# FPGA_interface.net
KiCad netlist of a schematic drawn in Altium Designer
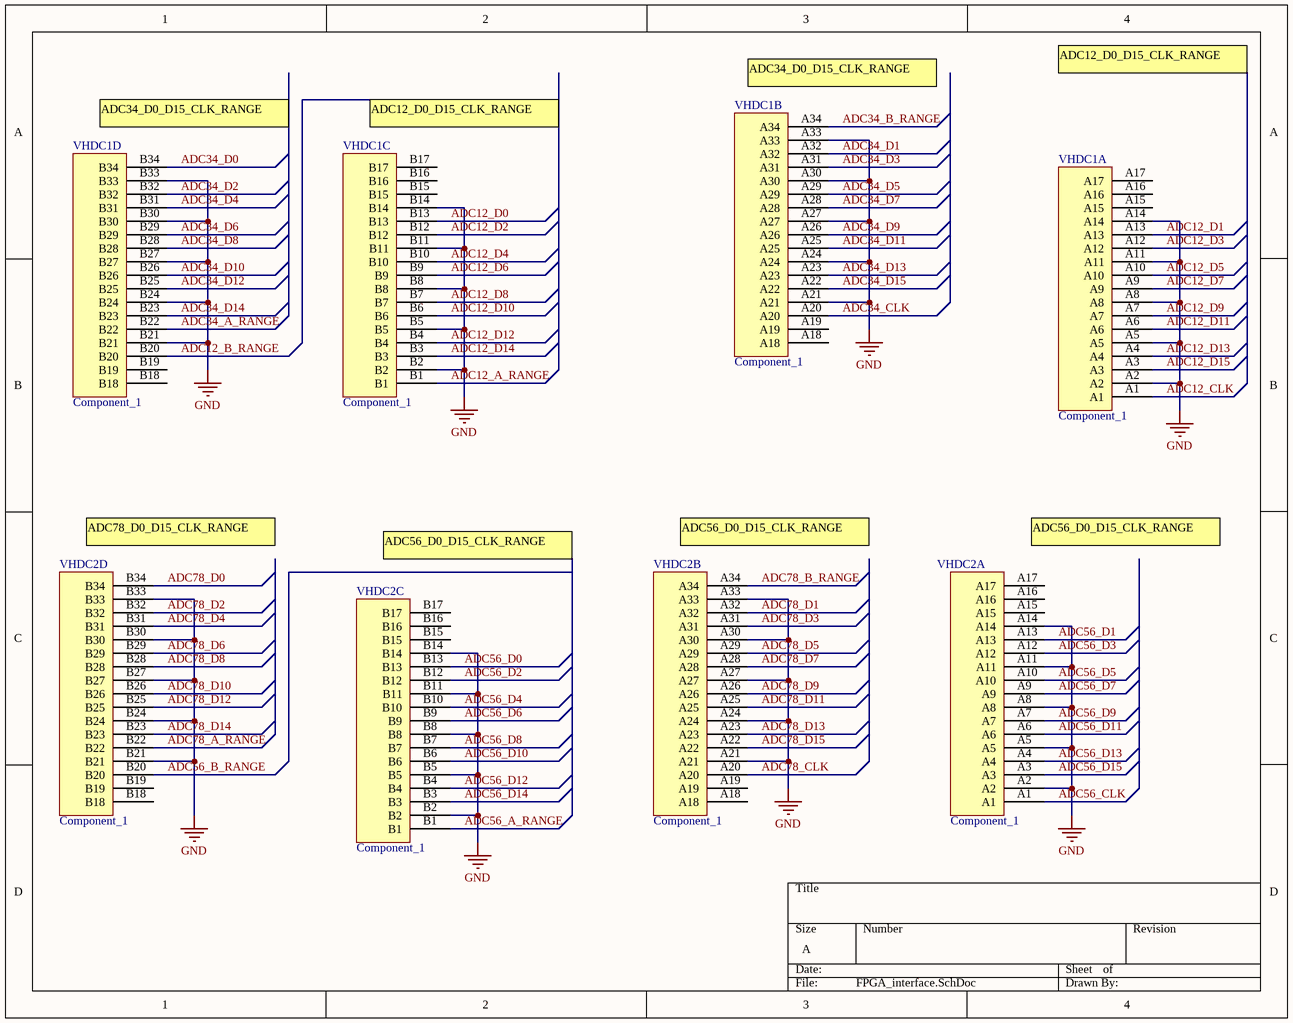
[diagram p0: FPGA_interface.SchDoc]

(export (version "E")
  (design (tool "Eeschema 10.0.6"))
  (components
    (comp (ref "VHDC1")
      (value "Component_1")
      (footprint "VHDCP-68-01-M-EM: PLUG")
      (description "VHDC_connector")
      (libsource (lib "MQP_lib") (part "Component_1"))
    )
    (comp (ref "VHDC2")
      (value "Component_1")
      (footprint "VHDCP-68-01-M-EM: PLUG")
      (description "VHDC_connector")
      (libsource (lib "MQP_lib") (part "Component_1"))
    )
  )
  (nets
    (net (code "1") (name "/ADC12_A_RANGE") (class "Default")
      (node (ref "VHDC1") (pin "B1") (pinfunction "B1_B1") (pintype "passive"))
    )
    (net (code "2") (name "/ADC12_B_RANGE") (class "Default")
      (node (ref "VHDC1") (pin "B20") (pinfunction "B20_B20") (pintype "passive"))
    )
    (net (code "3") (name "/ADC12_CLK") (class "Default")
      (node (ref "VHDC1") (pin "A1") (pinfunction "A1_A1") (pintype "passive"))
    )
    (net (code "4") (name "/ADC12_D0") (class "Default")
      (node (ref "VHDC1") (pin "B13") (pinfunction "B13_B13") (pintype "passive"))
    )
    (net (code "5") (name "/ADC12_D1") (class "Default")
      (node (ref "VHDC1") (pin "A13") (pinfunction "A13_A13") (pintype "passive"))
    )
    (net (code "6") (name "/ADC12_D2") (class "Default")
      (node (ref "VHDC1") (pin "B12") (pinfunction "B12_B12") (pintype "passive"))
    )
    (net (code "7") (name "/ADC12_D3") (class "Default")
      (node (ref "VHDC1") (pin "A12") (pinfunction "A12_A12") (pintype "passive"))
    )
    (net (code "8") (name "/ADC12_D4") (class "Default")
      (node (ref "VHDC1") (pin "B10") (pinfunction "B10_B10") (pintype "passive"))
    )
    (net (code "9") (name "/ADC12_D5") (class "Default")
      (node (ref "VHDC1") (pin "A10") (pinfunction "A10_A10") (pintype "passive"))
    )
    (net (code "10") (name "/ADC12_D6") (class "Default")
      (node (ref "VHDC1") (pin "B9") (pinfunction "B9_B9") (pintype "passive"))
    )
    (net (code "11") (name "/ADC12_D7") (class "Default")
      (node (ref "VHDC1") (pin "A9") (pinfunction "A9_A9") (pintype "passive"))
    )
    (net (code "12") (name "/ADC12_D8") (class "Default")
      (node (ref "VHDC1") (pin "B7") (pinfunction "B7_B7") (pintype "passive"))
    )
    (net (code "13") (name "/ADC12_D9") (class "Default")
      (node (ref "VHDC1") (pin "A7") (pinfunction "A7_A7") (pintype "passive"))
    )
    (net (code "14") (name "/ADC12_D10") (class "Default")
      (node (ref "VHDC1") (pin "B6") (pinfunction "B6_B6") (pintype "passive"))
    )
    (net (code "15") (name "/ADC12_D11") (class "Default")
      (node (ref "VHDC1") (pin "A6") (pinfunction "A6_A6") (pintype "passive"))
    )
    (net (code "16") (name "/ADC12_D12") (class "Default")
      (node (ref "VHDC1") (pin "B4") (pinfunction "B4_B4") (pintype "passive"))
    )
    (net (code "17") (name "/ADC12_D13") (class "Default")
      (node (ref "VHDC1") (pin "A4") (pinfunction "A4_A4") (pintype "passive"))
    )
    (net (code "18") (name "/ADC12_D14") (class "Default")
      (node (ref "VHDC1") (pin "B3") (pinfunction "B3_B3") (pintype "passive"))
    )
    (net (code "19") (name "/ADC12_D15") (class "Default")
      (node (ref "VHDC1") (pin "A3") (pinfunction "A3_A3") (pintype "passive"))
    )
    (net (code "20") (name "/ADC34_A_RANGE") (class "Default")
      (node (ref "VHDC1") (pin "B22") (pinfunction "B22_B22") (pintype "passive"))
    )
    (net (code "21") (name "/ADC34_B_RANGE") (class "Default")
      (node (ref "VHDC1") (pin "A34") (pinfunction "A34_A34") (pintype "passive"))
    )
    (net (code "22") (name "/ADC34_CLK") (class "Default")
      (node (ref "VHDC1") (pin "A20") (pinfunction "A20_A20") (pintype "passive"))
    )
    (net (code "23") (name "/ADC34_D0") (class "Default")
      (node (ref "VHDC1") (pin "B34") (pinfunction "B34_B34") (pintype "passive"))
    )
    (net (code "24") (name "/ADC34_D1") (class "Default")
      (node (ref "VHDC1") (pin "A32") (pinfunction "A32_A32") (pintype "passive"))
    )
    (net (code "25") (name "/ADC34_D2") (class "Default")
      (node (ref "VHDC1") (pin "B32") (pinfunction "B32_B32") (pintype "passive"))
    )
    (net (code "26") (name "/ADC34_D3") (class "Default")
      (node (ref "VHDC1") (pin "A31") (pinfunction "A31_A31") (pintype "passive"))
    )
    (net (code "27") (name "/ADC34_D4") (class "Default")
      (node (ref "VHDC1") (pin "B31") (pinfunction "B31_B31") (pintype "passive"))
    )
    (net (code "28") (name "/ADC34_D5") (class "Default")
      (node (ref "VHDC1") (pin "A29") (pinfunction "A29_A29") (pintype "passive"))
    )
    (net (code "29") (name "/ADC34_D6") (class "Default")
      (node (ref "VHDC1") (pin "B29") (pinfunction "B29_B29") (pintype "passive"))
    )
    (net (code "30") (name "/ADC34_D7") (class "Default")
      (node (ref "VHDC1") (pin "A28") (pinfunction "A28_A28") (pintype "passive"))
    )
    (net (code "31") (name "/ADC34_D8") (class "Default")
      (node (ref "VHDC1") (pin "B28") (pinfunction "B28_B28") (pintype "passive"))
    )
    (net (code "32") (name "/ADC34_D9") (class "Default")
      (node (ref "VHDC1") (pin "A26") (pinfunction "A26_A26") (pintype "passive"))
    )
    (net (code "33") (name "/ADC34_D10") (class "Default")
      (node (ref "VHDC1") (pin "B26") (pinfunction "B26_B26") (pintype "passive"))
    )
    (net (code "34") (name "/ADC34_D11") (class "Default")
      (node (ref "VHDC1") (pin "A25") (pinfunction "A25_A25") (pintype "passive"))
    )
    (net (code "35") (name "/ADC34_D12") (class "Default")
      (node (ref "VHDC1") (pin "B25") (pinfunction "B25_B25") (pintype "passive"))
    )
    (net (code "36") (name "/ADC34_D13") (class "Default")
      (node (ref "VHDC1") (pin "A23") (pinfunction "A23_A23") (pintype "passive"))
    )
    (net (code "37") (name "/ADC34_D14") (class "Default")
      (node (ref "VHDC1") (pin "B23") (pinfunction "B23_B23") (pintype "passive"))
    )
    (net (code "38") (name "/ADC34_D15") (class "Default")
      (node (ref "VHDC1") (pin "A22") (pinfunction "A22_A22") (pintype "passive"))
    )
    (net (code "39") (name "/ADC56_A_RANGE") (class "Default")
      (node (ref "VHDC2") (pin "B1") (pinfunction "B1_B1") (pintype "passive"))
    )
    (net (code "40") (name "/ADC56_B_RANGE") (class "Default")
      (node (ref "VHDC2") (pin "B20") (pinfunction "B20_B20") (pintype "passive"))
    )
    (net (code "41") (name "/ADC56_CLK") (class "Default")
      (node (ref "VHDC2") (pin "A1") (pinfunction "A1_A1") (pintype "passive"))
    )
    (net (code "42") (name "/ADC56_D0") (class "Default")
      (node (ref "VHDC2") (pin "B13") (pinfunction "B13_B13") (pintype "passive"))
    )
    (net (code "43") (name "/ADC56_D1") (class "Default")
      (node (ref "VHDC2") (pin "A13") (pinfunction "A13_A13") (pintype "passive"))
    )
    (net (code "44") (name "/ADC56_D2") (class "Default")
      (node (ref "VHDC2") (pin "B12") (pinfunction "B12_B12") (pintype "passive"))
    )
    (net (code "45") (name "/ADC56_D3") (class "Default")
      (node (ref "VHDC2") (pin "A12") (pinfunction "A12_A12") (pintype "passive"))
    )
    (net (code "46") (name "/ADC56_D4") (class "Default")
      (node (ref "VHDC2") (pin "B10") (pinfunction "B10_B10") (pintype "passive"))
    )
    (net (code "47") (name "/ADC56_D5") (class "Default")
      (node (ref "VHDC2") (pin "A10") (pinfunction "A10_A10") (pintype "passive"))
    )
    (net (code "48") (name "/ADC56_D6") (class "Default")
      (node (ref "VHDC2") (pin "B9") (pinfunction "B9_B9") (pintype "passive"))
    )
    (net (code "49") (name "/ADC56_D7") (class "Default")
      (node (ref "VHDC2") (pin "A9") (pinfunction "A9_A9") (pintype "passive"))
    )
    (net (code "50") (name "/ADC56_D8") (class "Default")
      (node (ref "VHDC2") (pin "B7") (pinfunction "B7_B7") (pintype "passive"))
    )
    (net (code "51") (name "/ADC56_D9") (class "Default")
      (node (ref "VHDC2") (pin "A7") (pinfunction "A7_A7") (pintype "passive"))
    )
    (net (code "52") (name "/ADC56_D10") (class "Default")
      (node (ref "VHDC2") (pin "B6") (pinfunction "B6_B6") (pintype "passive"))
    )
    (net (code "53") (name "/ADC56_D11") (class "Default")
      (node (ref "VHDC2") (pin "A6") (pinfunction "A6_A6") (pintype "passive"))
    )
    (net (code "54") (name "/ADC56_D12") (class "Default")
      (node (ref "VHDC2") (pin "B4") (pinfunction "B4_B4") (pintype "passive"))
    )
    (net (code "55") (name "/ADC56_D13") (class "Default")
      (node (ref "VHDC2") (pin "A4") (pinfunction "A4_A4") (pintype "passive"))
    )
    (net (code "56") (name "/ADC56_D14") (class "Default")
      (node (ref "VHDC2") (pin "B3") (pinfunction "B3_B3") (pintype "passive"))
    )
    (net (code "57") (name "/ADC56_D15") (class "Default")
      (node (ref "VHDC2") (pin "A3") (pinfunction "A3_A3") (pintype "passive"))
    )
    (net (code "58") (name "/ADC78_A_RANGE") (class "Default")
      (node (ref "VHDC2") (pin "B22") (pinfunction "B22_B22") (pintype "passive"))
    )
    (net (code "59") (name "/ADC78_B_RANGE") (class "Default")
      (node (ref "VHDC2") (pin "A34") (pinfunction "A34_A34") (pintype "passive"))
    )
    (net (code "60") (name "/ADC78_CLK") (class "Default")
      (node (ref "VHDC2") (pin "A20") (pinfunction "A20_A20") (pintype "passive"))
    )
    (net (code "61") (name "/ADC78_D0") (class "Default")
      (node (ref "VHDC2") (pin "B34") (pinfunction "B34_B34") (pintype "passive"))
    )
    (net (code "62") (name "/ADC78_D1") (class "Default")
      (node (ref "VHDC2") (pin "A32") (pinfunction "A32_A32") (pintype "passive"))
    )
    (net (code "63") (name "/ADC78_D2") (class "Default")
      (node (ref "VHDC2") (pin "B32") (pinfunction "B32_B32") (pintype "passive"))
    )
    (net (code "64") (name "/ADC78_D3") (class "Default")
      (node (ref "VHDC2") (pin "A31") (pinfunction "A31_A31") (pintype "passive"))
    )
    (net (code "65") (name "/ADC78_D4") (class "Default")
      (node (ref "VHDC2") (pin "B31") (pinfunction "B31_B31") (pintype "passive"))
    )
    (net (code "66") (name "/ADC78_D5") (class "Default")
      (node (ref "VHDC2") (pin "A29") (pinfunction "A29_A29") (pintype "passive"))
    )
    (net (code "67") (name "/ADC78_D6") (class "Default")
      (node (ref "VHDC2") (pin "B29") (pinfunction "B29_B29") (pintype "passive"))
    )
    (net (code "68") (name "/ADC78_D7") (class "Default")
      (node (ref "VHDC2") (pin "A28") (pinfunction "A28_A28") (pintype "passive"))
    )
    (net (code "69") (name "/ADC78_D8") (class "Default")
      (node (ref "VHDC2") (pin "B28") (pinfunction "B28_B28") (pintype "passive"))
    )
    (net (code "70") (name "/ADC78_D9") (class "Default")
      (node (ref "VHDC2") (pin "A26") (pinfunction "A26_A26") (pintype "passive"))
    )
    (net (code "71") (name "/ADC78_D10") (class "Default")
      (node (ref "VHDC2") (pin "B26") (pinfunction "B26_B26") (pintype "passive"))
    )
    (net (code "72") (name "/ADC78_D11") (class "Default")
      (node (ref "VHDC2") (pin "A25") (pinfunction "A25_A25") (pintype "passive"))
    )
    (net (code "73") (name "/ADC78_D12") (class "Default")
      (node (ref "VHDC2") (pin "B25") (pinfunction "B25_B25") (pintype "passive"))
    )
    (net (code "74") (name "/ADC78_D13") (class "Default")
      (node (ref "VHDC2") (pin "A23") (pinfunction "A23_A23") (pintype "passive"))
    )
    (net (code "75") (name "/ADC78_D14") (class "Default")
      (node (ref "VHDC2") (pin "B23") (pinfunction "B23_B23") (pintype "passive"))
    )
    (net (code "76") (name "/ADC78_D15") (class "Default")
      (node (ref "VHDC2") (pin "A22") (pinfunction "A22_A22") (pintype "passive"))
    )
    (net (code "77") (name "GND") (class "Default")
      (node (ref "VHDC1") (pin "A11") (pinfunction "A11_A11") (pintype "passive"))
      (node (ref "VHDC1") (pin "A14") (pinfunction "A14_A14") (pintype "passive"))
      (node (ref "VHDC1") (pin "A2") (pinfunction "A2_A2") (pintype "passive"))
      (node (ref "VHDC1") (pin "A21") (pinfunction "A21_A21") (pintype "passive"))
      (node (ref "VHDC1") (pin "A24") (pinfunction "A24_A24") (pintype "passive"))
      (node (ref "VHDC1") (pin "A27") (pinfunction "A27_A27") (pintype "passive"))
      (node (ref "VHDC1") (pin "A30") (pinfunction "A30_A30") (pintype "passive"))
      (node (ref "VHDC1") (pin "A33") (pinfunction "A33_A33") (pintype "passive"))
      (node (ref "VHDC1") (pin "A5") (pinfunction "A5_A5") (pintype "passive"))
      (node (ref "VHDC1") (pin "A8") (pinfunction "A8_A8") (pintype "passive"))
      (node (ref "VHDC1") (pin "B11") (pinfunction "B11_B11") (pintype "passive"))
      (node (ref "VHDC1") (pin "B14") (pinfunction "B14_B14") (pintype "passive"))
      (node (ref "VHDC1") (pin "B2") (pinfunction "B2_B2") (pintype "passive"))
      (node (ref "VHDC1") (pin "B21") (pinfunction "B21_B21") (pintype "passive"))
      (node (ref "VHDC1") (pin "B24") (pinfunction "B24_B24") (pintype "passive"))
      (node (ref "VHDC1") (pin "B27") (pinfunction "B27_B27") (pintype "passive"))
      (node (ref "VHDC1") (pin "B30") (pinfunction "B30_B30") (pintype "passive"))
      (node (ref "VHDC1") (pin "B33") (pinfunction "B33_B33") (pintype "passive"))
      (node (ref "VHDC1") (pin "B5") (pinfunction "B5_B5") (pintype "passive"))
      (node (ref "VHDC1") (pin "B8") (pinfunction "B8_B8") (pintype "passive"))
      (node (ref "VHDC2") (pin "A11") (pinfunction "A11_A11") (pintype "passive"))
      (node (ref "VHDC2") (pin "A14") (pinfunction "A14_A14") (pintype "passive"))
      (node (ref "VHDC2") (pin "A2") (pinfunction "A2_A2") (pintype "passive"))
      (node (ref "VHDC2") (pin "A21") (pinfunction "A21_A21") (pintype "passive"))
      (node (ref "VHDC2") (pin "A24") (pinfunction "A24_A24") (pintype "passive"))
      (node (ref "VHDC2") (pin "A27") (pinfunction "A27_A27") (pintype "passive"))
      (node (ref "VHDC2") (pin "A30") (pinfunction "A30_A30") (pintype "passive"))
      (node (ref "VHDC2") (pin "A33") (pinfunction "A33_A33") (pintype "passive"))
      (node (ref "VHDC2") (pin "A5") (pinfunction "A5_A5") (pintype "passive"))
      (node (ref "VHDC2") (pin "A8") (pinfunction "A8_A8") (pintype "passive"))
      (node (ref "VHDC2") (pin "B11") (pinfunction "B11_B11") (pintype "passive"))
      (node (ref "VHDC2") (pin "B14") (pinfunction "B14_B14") (pintype "passive"))
      (node (ref "VHDC2") (pin "B2") (pinfunction "B2_B2") (pintype "passive"))
      (node (ref "VHDC2") (pin "B21") (pinfunction "B21_B21") (pintype "passive"))
      (node (ref "VHDC2") (pin "B24") (pinfunction "B24_B24") (pintype "passive"))
      (node (ref "VHDC2") (pin "B27") (pinfunction "B27_B27") (pintype "passive"))
      (node (ref "VHDC2") (pin "B30") (pinfunction "B30_B30") (pintype "passive"))
      (node (ref "VHDC2") (pin "B33") (pinfunction "B33_B33") (pintype "passive"))
      (node (ref "VHDC2") (pin "B5") (pinfunction "B5_B5") (pintype "passive"))
      (node (ref "VHDC2") (pin "B8") (pinfunction "B8_B8") (pintype "passive"))
    )
    (net (code "78") (name "unconnected-(VHDC1-PadA15)") (class "Default")
      (node (ref "VHDC1") (pin "A15") (pinfunction "A15_A15") (pintype "passive"))
    )
    (net (code "79") (name "unconnected-(VHDC1-PadA16)") (class "Default")
      (node (ref "VHDC1") (pin "A16") (pinfunction "A16_A16") (pintype "passive"))
    )
    (net (code "80") (name "unconnected-(VHDC1-PadA17)") (class "Default")
      (node (ref "VHDC1") (pin "A17") (pinfunction "A17_A17") (pintype "passive"))
    )
    (net (code "81") (name "unconnected-(VHDC1-PadA18)") (class "Default")
      (node (ref "VHDC1") (pin "A18") (pinfunction "A18_A18") (pintype "passive"))
    )
    (net (code "82") (name "unconnected-(VHDC1-PadA19)") (class "Default")
      (node (ref "VHDC1") (pin "A19") (pinfunction "A19_A19") (pintype "passive"))
    )
    (net (code "83") (name "unconnected-(VHDC1-PadB15)") (class "Default")
      (node (ref "VHDC1") (pin "B15") (pinfunction "B15_B15") (pintype "passive"))
    )
    (net (code "84") (name "unconnected-(VHDC1-PadB16)") (class "Default")
      (node (ref "VHDC1") (pin "B16") (pinfunction "B16_B16") (pintype "passive"))
    )
    (net (code "85") (name "unconnected-(VHDC1-PadB17)") (class "Default")
      (node (ref "VHDC1") (pin "B17") (pinfunction "B17_B17") (pintype "passive"))
    )
    (net (code "86") (name "unconnected-(VHDC1-PadB18)") (class "Default")
      (node (ref "VHDC1") (pin "B18") (pinfunction "B18_B18") (pintype "passive"))
    )
    (net (code "87") (name "unconnected-(VHDC1-PadB19)") (class "Default")
      (node (ref "VHDC1") (pin "B19") (pinfunction "B19_B19") (pintype "passive"))
    )
    (net (code "88") (name "unconnected-(VHDC2-PadA15)") (class "Default")
      (node (ref "VHDC2") (pin "A15") (pinfunction "A15_A15") (pintype "passive"))
    )
    (net (code "89") (name "unconnected-(VHDC2-PadA16)") (class "Default")
      (node (ref "VHDC2") (pin "A16") (pinfunction "A16_A16") (pintype "passive"))
    )
    (net (code "90") (name "unconnected-(VHDC2-PadA17)") (class "Default")
      (node (ref "VHDC2") (pin "A17") (pinfunction "A17_A17") (pintype "passive"))
    )
    (net (code "91") (name "unconnected-(VHDC2-PadA18)") (class "Default")
      (node (ref "VHDC2") (pin "A18") (pinfunction "A18_A18") (pintype "passive"))
    )
    (net (code "92") (name "unconnected-(VHDC2-PadA19)") (class "Default")
      (node (ref "VHDC2") (pin "A19") (pinfunction "A19_A19") (pintype "passive"))
    )
    (net (code "93") (name "unconnected-(VHDC2-PadB15)") (class "Default")
      (node (ref "VHDC2") (pin "B15") (pinfunction "B15_B15") (pintype "passive"))
    )
    (net (code "94") (name "unconnected-(VHDC2-PadB16)") (class "Default")
      (node (ref "VHDC2") (pin "B16") (pinfunction "B16_B16") (pintype "passive"))
    )
    (net (code "95") (name "unconnected-(VHDC2-PadB17)") (class "Default")
      (node (ref "VHDC2") (pin "B17") (pinfunction "B17_B17") (pintype "passive"))
    )
    (net (code "96") (name "unconnected-(VHDC2-PadB18)") (class "Default")
      (node (ref "VHDC2") (pin "B18") (pinfunction "B18_B18") (pintype "passive"))
    )
    (net (code "97") (name "unconnected-(VHDC2-PadB19)") (class "Default")
      (node (ref "VHDC2") (pin "B19") (pinfunction "B19_B19") (pintype "passive"))
    )
  )
)
